# Power_Pcb.net
KiCad netlist of a schematic drawn in Altium Designer
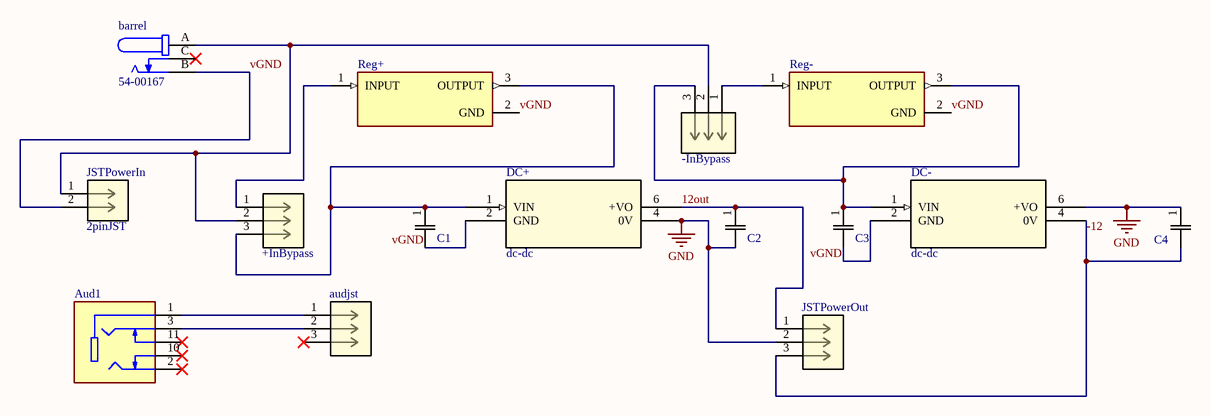
[diagram p0: Power_Pcb.SchDoc]

(export (version "E")
  (design (tool "Eeschema 10.0.6"))
  (components
    (comp (ref "+InBypass")
      (value "3pinHeaders")
      (footprint "CONN_M20-99903XX_HRW")
      (description "No Description Available")
      (libsource (lib "AnalogProject") (part "3pinHeaders"))
    )
    (comp (ref "-InBypass")
      (value "3pinHeaders")
      (footprint "CONN_M20-99903XX_HRW")
      (description "No Description Available")
      (libsource (lib "") (part "3pinHeaders_1"))
    )
    (comp (ref "Aud1")
      (value "Audioport")
      (footprint "CUI_SJ1-3525N")
      (description "3.5 mm, Stereo, Right Angle, Through Hole, 3 Conductors, 2 Internal Switches, Audio Jack Connector")
      (fields (field (name "MF") "CUI Devices") (field (name "MP") "SJ1-3525N"))
      (libsource (lib "AnalogProject") (part "Audioport"))
    )
    (comp (ref "audjst")
      (value "3pinHeaders")
      (footprint "CONN_M20-99903XX_HRW")
      (description "No Description Available")
      (libsource (lib "AnalogProject") (part "3pinHeaders"))
    )
    (comp (ref "barrel")
      (value "54-00167")
      (footprint "TENSILITY_54-00167")
      (description "Connector, dc jack 5.5x2.5 mm, PCB mount, 90 degrees, nickel plated, PBT, thru hole")
      (fields (field (name "MF") "Tensility International Corp"))
      (libsource (lib "AnalogProject") (part "54-00167"))
    )
    (comp (ref "C1")
      (value "capacitor")
      (footprint "CAP_YX_6P3X11_RUB")
      (description "No Description Available")
      (libsource (lib "AnalogProject") (part "capacitor"))
    )
    (comp (ref "C2")
      (value "capacitor")
      (footprint "CAP_YX_6P3X11_RUB")
      (description "No Description Available")
      (libsource (lib "AnalogProject") (part "capacitor"))
    )
    (comp (ref "C3")
      (value "capacitor")
      (footprint "CAP_YX_6P3X11_RUB")
      (description "No Description Available")
      (libsource (lib "AnalogProject") (part "capacitor"))
    )
    (comp (ref "C4")
      (value "capacitor")
      (footprint "CAP_YX_6P3X11_RUB")
      (description "No Description Available")
      (libsource (lib "AnalogProject") (part "capacitor"))
    )
    (comp (ref "DC+")
      (value "dc-dc")
      (footprint "B_S-2WR2_MNS")
      (description "No Description Available")
      (libsource (lib "AnalogProject") (part "dc-dc"))
    )
    (comp (ref "DC-")
      (value "dc-dc")
      (footprint "B_S-2WR2_MNS")
      (description "No Description Available")
      (libsource (lib "AnalogProject") (part "dc-dc"))
    )
    (comp (ref "JSTPowerIn")
      (value "2pinJST")
      (footprint "CONN_B2B-XH-A_JST")
      (description "No Description Available")
      (libsource (lib "AnalogProject") (part "2pinJST"))
    )
    (comp (ref "JSTPowerOut")
      (value "3pinJST")
      (footprint "CONN_B3B-XH-A_JST")
      (description "No Description Available")
      (libsource (lib "AnalogProject") (part "3pinJST"))
    )
    (comp (ref "Reg+")
      (value "+10vregulator")
      (footprint "TO255P1020X450X1968-3B")
      (description "Linear Voltage Regulator IC Positive Fixed 1 Output 1.5A TO-220AB")
      (fields (field (name "MF") "STMicroelectronics") (field (name "MP") "L7810CV"))
      (libsource (lib "AnalogProject") (part "+10vregulator"))
    )
    (comp (ref "Reg-")
      (value "+10vregulator")
      (footprint "TO255P1020X450X1968-3B")
      (description "Linear Voltage Regulator IC Positive Fixed 1 Output 1.5A TO-220AB")
      (fields (field (name "MF") "STMicroelectronics") (field (name "MP") "L7810CV"))
      (libsource (lib "AnalogProject") (part "+10vregulator"))
    )
  )
  (nets
    (net (code "1") (name "/-12") (class "Default")
      (node (ref "C4") (pin "2") (pinfunction "2_2") (pintype "passive"))
      (node (ref "DC-") (pin "4") (pinfunction "0V_4") (pintype "passive"))
      (node (ref "JSTPowerOut") (pin "3") (pinfunction "3_3") (pintype "passive"))
    )
    (net (code "2") (name "/12out") (class "Default")
      (node (ref "C2") (pin "1") (pinfunction "1_1") (pintype "passive"))
      (node (ref "DC+") (pin "6") (pinfunction "+VO_6") (pintype "power_in"))
      (node (ref "JSTPowerOut") (pin "1") (pinfunction "1_1") (pintype "passive"))
    )
    (net (code "3") (name "/vGND") (class "Default")
      (node (ref "C1") (pin "2") (pinfunction "2_2") (pintype "passive"))
      (node (ref "C3") (pin "2") (pinfunction "2_2") (pintype "passive"))
      (node (ref "DC+") (pin "2") (pinfunction "GND_2") (pintype "power_in"))
      (node (ref "DC-") (pin "2") (pinfunction "GND_2") (pintype "power_in"))
      (node (ref "JSTPowerIn") (pin "2") (pinfunction "2_2") (pintype "passive"))
      (node (ref "Reg+") (pin "2") (pinfunction "GND_2") (pintype "power_in"))
      (node (ref "Reg-") (pin "2") (pinfunction "GND_2") (pintype "power_in"))
      (node (ref "barrel") (pin "B") (pinfunction "B_B") (pintype "passive"))
    )
    (net (code "4") (name "GND") (class "Default")
      (node (ref "C2") (pin "2") (pinfunction "2_2") (pintype "passive"))
      (node (ref "C4") (pin "1") (pinfunction "1_1") (pintype "passive"))
      (node (ref "DC+") (pin "4") (pinfunction "0V_4") (pintype "passive"))
      (node (ref "DC-") (pin "6") (pinfunction "+VO_6") (pintype "power_in"))
      (node (ref "JSTPowerOut") (pin "2") (pinfunction "2_2") (pintype "passive"))
    )
    (net (code "5") (name "Net-(+InBypass-Pad2)") (class "Default")
      (node (ref "+InBypass") (pin "2") (pinfunction "2_2") (pintype "passive"))
      (node (ref "-InBypass") (pin "2") (pinfunction "2_2") (pintype "passive"))
      (node (ref "JSTPowerIn") (pin "1") (pinfunction "1_1") (pintype "passive"))
      (node (ref "barrel") (pin "A") (pinfunction "A_A") (pintype "passive"))
    )
    (net (code "6") (name "Net-(Aud1-Pad1)") (class "Default")
      (node (ref "Aud1") (pin "1") (pinfunction "1_1") (pintype "passive"))
      (node (ref "audjst") (pin "1") (pinfunction "1_1") (pintype "passive"))
    )
    (net (code "7") (name "Net-(Aud1-Pad3)") (class "Default")
      (node (ref "Aud1") (pin "3") (pinfunction "3_3") (pintype "passive"))
      (node (ref "audjst") (pin "2") (pinfunction "2_2") (pintype "passive"))
    )
    (net (code "8") (name "Net-(DC+-VIN)") (class "Default")
      (node (ref "+InBypass") (pin "3") (pinfunction "3_3") (pintype "passive"))
      (node (ref "C1") (pin "1") (pinfunction "1_1") (pintype "passive"))
      (node (ref "DC+") (pin "1") (pinfunction "VIN_1") (pintype "input"))
      (node (ref "Reg+") (pin "3") (pinfunction "OUTPUT_3") (pintype "output"))
    )
    (net (code "9") (name "Net-(DC--VIN)") (class "Default")
      (node (ref "-InBypass") (pin "3") (pinfunction "3_3") (pintype "passive"))
      (node (ref "C3") (pin "1") (pinfunction "1_1") (pintype "passive"))
      (node (ref "DC-") (pin "1") (pinfunction "VIN_1") (pintype "input"))
      (node (ref "Reg-") (pin "3") (pinfunction "OUTPUT_3") (pintype "output"))
    )
    (net (code "10") (name "Net-(Reg+-INPUT)") (class "Default")
      (node (ref "+InBypass") (pin "1") (pinfunction "1_1") (pintype "passive"))
      (node (ref "Reg+") (pin "1") (pinfunction "INPUT_1") (pintype "input"))
    )
    (net (code "11") (name "Net-(Reg--INPUT)") (class "Default")
      (node (ref "-InBypass") (pin "1") (pinfunction "1_1") (pintype "passive"))
      (node (ref "Reg-") (pin "1") (pinfunction "INPUT_1") (pintype "input"))
    )
    (net (code "12") (name "unconnected-(Aud1-Pad2)") (class "Default")
      (node (ref "Aud1") (pin "2") (pinfunction "2_2") (pintype "passive+no_connect"))
    )
    (net (code "13") (name "unconnected-(Aud1-Pad10)") (class "Default")
      (node (ref "Aud1") (pin "10") (pinfunction "10_10") (pintype "passive+no_connect"))
    )
    (net (code "14") (name "unconnected-(Aud1-Pad11)") (class "Default")
      (node (ref "Aud1") (pin "11") (pinfunction "11_11") (pintype "passive+no_connect"))
    )
    (net (code "15") (name "unconnected-(audjst-Pad3)") (class "Default")
      (node (ref "audjst") (pin "3") (pinfunction "3_3") (pintype "passive+no_connect"))
    )
    (net (code "16") (name "unconnected-(barrel-PadC)") (class "Default")
      (node (ref "barrel") (pin "C") (pinfunction "C_C") (pintype "passive+no_connect"))
    )
  )
)
